# SchmitOpto.net
KiCad netlist of a schematic drawn in Altium Designer
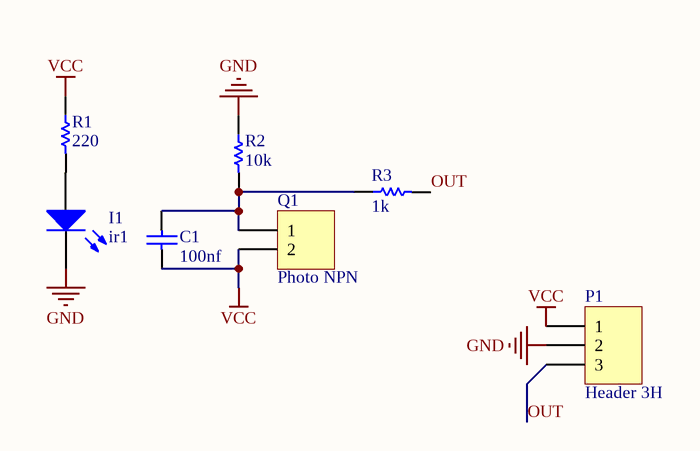
[diagram p0: SchmitOpto.SchDoc]

(export (version "E")
  (design (tool "Eeschema 10.0.6"))
  (components
    (comp (ref "C1")
      (value "100nf")
      (footprint "6-0805_M")
      (description "Capacitor")
      (fields (field (name "Comment") "Cap") (field (name "PUBLISHER") "Altium Limited"))
      (libsource (lib "Miscellaneous Devices") (part "Cap"))
    )
    (comp (ref "I1")
      (value "ir1")
      (footprint "HDR1X2")
      (description "Typical INFRARED GaAs LED")
      (fields (field (name "PUBLISHER") "Altium Limited"))
      (libsource (lib "Miscellaneous Devices") (part "LED0"))
    )
    (comp (ref "P1")
      (value "Header 3H")
      (footprint "HDR1X3H")
      (description "Header, 3-Pin, Right Angle")
      (fields (field (name "PUBLISHER") "Altium Limited"))
      (libsource (lib "Miscellaneous Connectors") (part "Header 3H"))
    )
    (comp (ref "Q1")
      (value "Photo NPN")
      (footprint "HDR1X2")
      (description "Header, 2-Pin")
      (fields (field (name "PUBLISHER") "Altium Limited"))
      (libsource (lib "Miscellaneous Connectors") (part "Header 2"))
    )
    (comp (ref "R1")
      (value "220")
      (footprint "6-0805_M")
      (description "Resistor")
      (fields (field (name "PUBLISHER") "Altium Limited"))
      (libsource (lib "Miscellaneous Devices") (part "Res1"))
    )
    (comp (ref "R2")
      (value "10k")
      (footprint "6-0805_M")
      (description "Resistor")
      (fields (field (name "Comment") "10K") (field (name "PUBLISHER") "Altium Limited"))
      (libsource (lib "Miscellaneous Devices") (part "Res1"))
    )
    (comp (ref "R3")
      (value "1k")
      (footprint "6-0805_M")
      (description "Resistor")
      (fields (field (name "Comment") "1K") (field (name "PUBLISHER") "Altium Limited"))
      (libsource (lib "Miscellaneous Devices") (part "Res1"))
    )
  )
  (nets
    (net (code "1") (name "/OUT") (class "Default")
      (node (ref "P1") (pin "3") (pinfunction "3_3") (pintype "passive"))
      (node (ref "R3") (pin "2") (pinfunction "2_2") (pintype "passive"))
    )
    (net (code "2") (name "GND") (class "Default")
      (node (ref "I1") (pin "2") (pinfunction "K_2") (pintype "passive"))
      (node (ref "P1") (pin "2") (pinfunction "2_2") (pintype "passive"))
      (node (ref "R2") (pin "1") (pinfunction "1_1") (pintype "passive"))
    )
    (net (code "3") (name "Net-(C1-Pad1)") (class "Default")
      (node (ref "C1") (pin "1") (pinfunction "1_1") (pintype "passive"))
      (node (ref "Q1") (pin "1") (pinfunction "1_1") (pintype "passive"))
      (node (ref "R2") (pin "2") (pinfunction "2_2") (pintype "passive"))
      (node (ref "R3") (pin "1") (pinfunction "1_1") (pintype "passive"))
    )
    (net (code "4") (name "Net-(I1-A)") (class "Default")
      (node (ref "I1") (pin "1") (pinfunction "A_1") (pintype "passive"))
      (node (ref "R1") (pin "2") (pinfunction "2_2") (pintype "passive"))
    )
    (net (code "5") (name "VCC") (class "Default")
      (node (ref "C1") (pin "2") (pinfunction "2_2") (pintype "passive"))
      (node (ref "P1") (pin "1") (pinfunction "1_1") (pintype "passive"))
      (node (ref "Q1") (pin "2") (pinfunction "2_2") (pintype "passive"))
      (node (ref "R1") (pin "1") (pinfunction "1_1") (pintype "passive"))
    )
  )
)
